# Business_Card.net
KiCad netlist of a schematic drawn in EAGLE
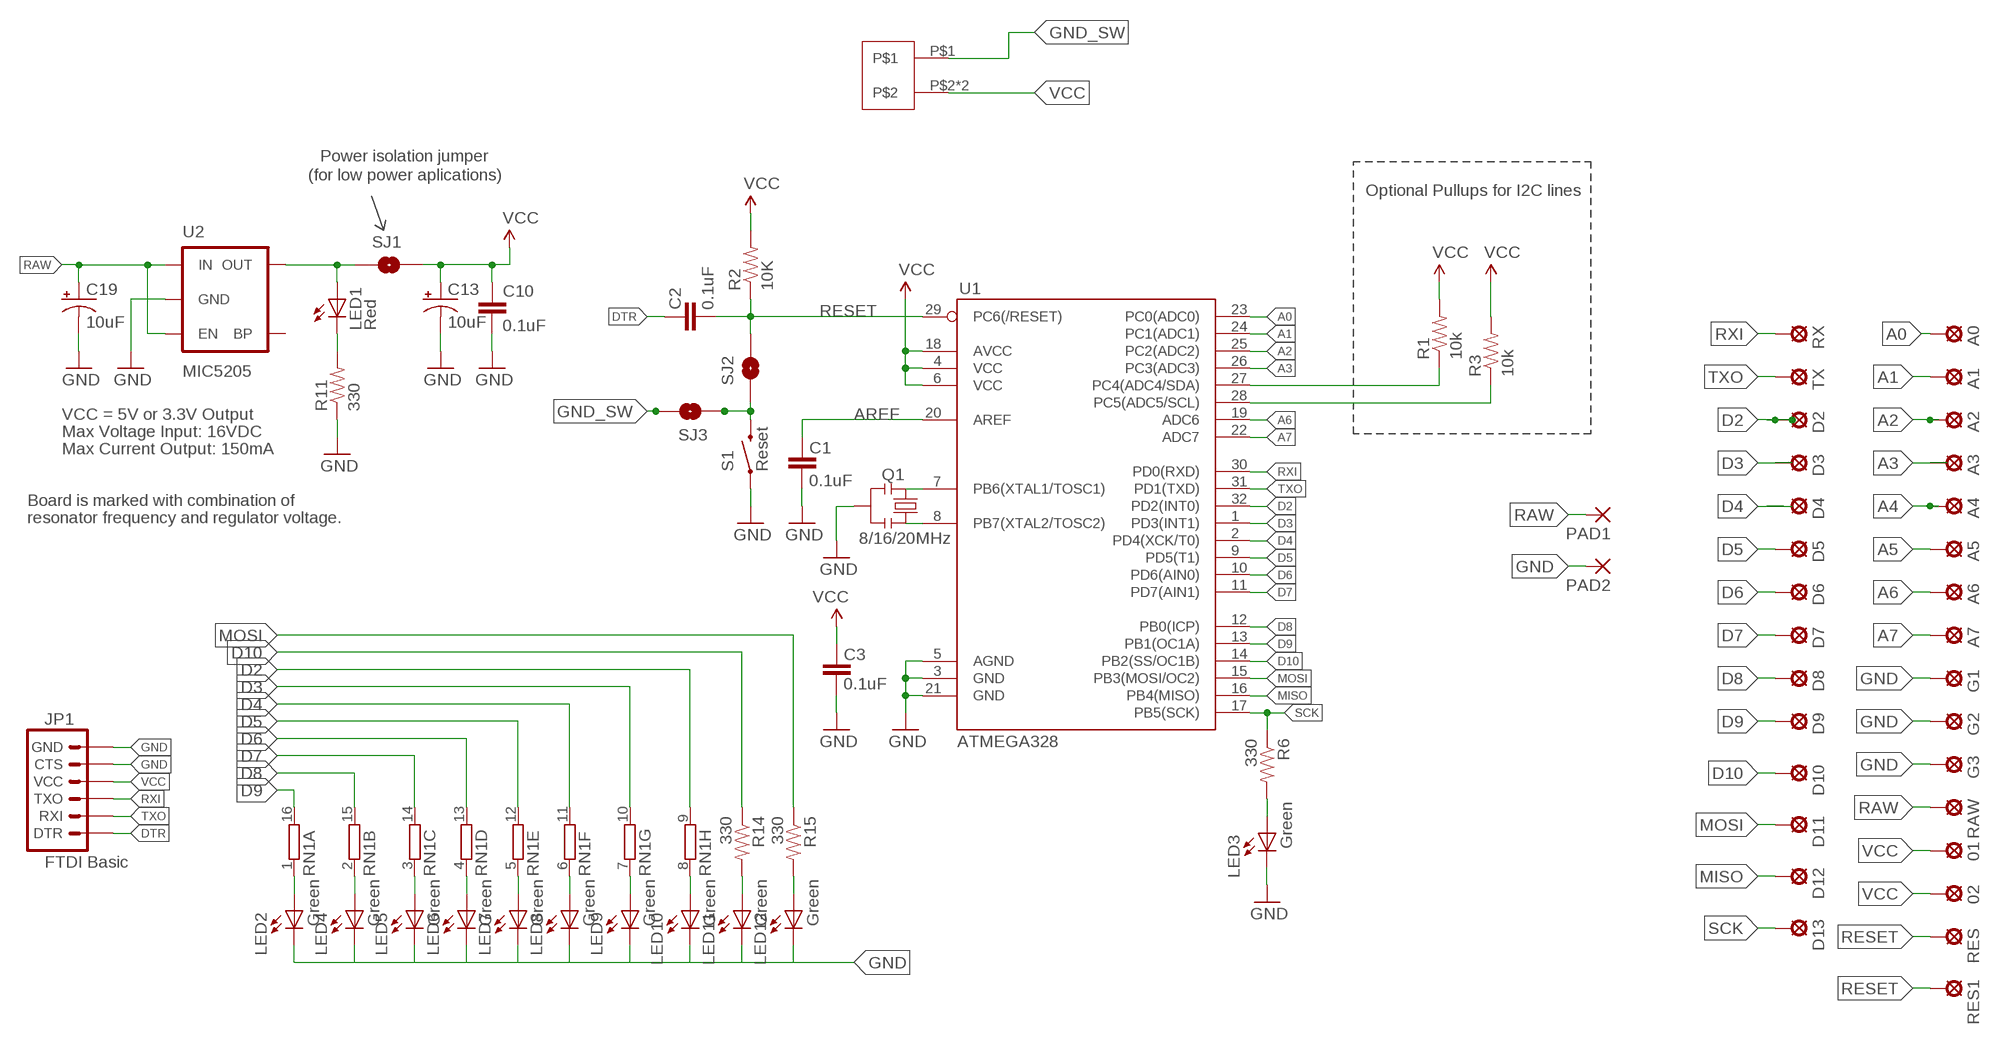
[diagram p0: schematic, sheet 1]

(export (version "E")
  (design (tool "Eeschema 10.0.6"))
  (components
    (comp (ref "01")
      (value "SE13")
      (footprint "eagle-import:SE13")
      (libsource (lib "eagle-import") (part "SE13"))
    )
    (comp (ref "02")
      (value "SE13")
      (footprint "eagle-import:SE13")
      (libsource (lib "eagle-import") (part "SE13"))
    )
    (comp (ref "A0")
      (value "SE13")
      (footprint "eagle-import:SE13")
      (libsource (lib "eagle-import") (part "SE13"))
    )
    (comp (ref "A1")
      (value "SE13")
      (footprint "eagle-import:SE13")
      (libsource (lib "eagle-import") (part "SE13"))
    )
    (comp (ref "A2")
      (value "SE13")
      (footprint "eagle-import:SE13")
      (libsource (lib "eagle-import") (part "SE13"))
    )
    (comp (ref "A3")
      (value "SE13")
      (footprint "eagle-import:SE13")
      (libsource (lib "eagle-import") (part "SE13"))
    )
    (comp (ref "A4")
      (value "SE13")
      (footprint "eagle-import:SE13")
      (libsource (lib "eagle-import") (part "SE13"))
    )
    (comp (ref "A5")
      (value "SE13")
      (footprint "eagle-import:SE13")
      (libsource (lib "eagle-import") (part "SE13"))
    )
    (comp (ref "A6")
      (value "SE13")
      (footprint "eagle-import:SE13")
      (libsource (lib "eagle-import") (part "SE13"))
    )
    (comp (ref "A7")
      (value "SE13")
      (footprint "eagle-import:SE13")
      (libsource (lib "eagle-import") (part "SE13"))
    )
    (comp (ref "C1")
      (value "0.1uF")
      (footprint "eagle-import:0603-CAP")
      (libsource (lib "eagle-import") (part "CAP0603-CAP"))
    )
    (comp (ref "C2")
      (value "0.1uF")
      (footprint "eagle-import:0603-CAP")
      (libsource (lib "eagle-import") (part "CAP0603-CAP"))
    )
    (comp (ref "C3")
      (value "0.1uF")
      (footprint "eagle-import:0603-CAP")
      (libsource (lib "eagle-import") (part "CAP0603-CAP"))
    )
    (comp (ref "C10")
      (value "0.1uF")
      (footprint "eagle-import:0603-CAP")
      (libsource (lib "eagle-import") (part "CAP0603-CAP"))
    )
    (comp (ref "C13")
      (value "10uF")
      (footprint "eagle-import:EIA3216")
      (libsource (lib "eagle-import") (part "CAP_POL1206"))
    )
    (comp (ref "C19")
      (value "10uF")
      (footprint "eagle-import:EIA3216")
      (libsource (lib "eagle-import") (part "CAP_POL1206"))
    )
    (comp (ref "D2")
      (value "SE13")
      (footprint "eagle-import:SE13")
      (libsource (lib "eagle-import") (part "SE13"))
    )
    (comp (ref "D3")
      (value "SE13")
      (footprint "eagle-import:SE13")
      (libsource (lib "eagle-import") (part "SE13"))
    )
    (comp (ref "D4")
      (value "SE13")
      (footprint "eagle-import:SE13")
      (libsource (lib "eagle-import") (part "SE13"))
    )
    (comp (ref "D5")
      (value "SE13")
      (footprint "eagle-import:SE13")
      (libsource (lib "eagle-import") (part "SE13"))
    )
    (comp (ref "D6")
      (value "SE13")
      (footprint "eagle-import:SE13")
      (libsource (lib "eagle-import") (part "SE13"))
    )
    (comp (ref "D7")
      (value "SE13")
      (footprint "eagle-import:SE13")
      (libsource (lib "eagle-import") (part "SE13"))
    )
    (comp (ref "D8")
      (value "SE13")
      (footprint "eagle-import:SE13")
      (libsource (lib "eagle-import") (part "SE13"))
    )
    (comp (ref "D9")
      (value "SE13")
      (footprint "eagle-import:SE13")
      (libsource (lib "eagle-import") (part "SE13"))
    )
    (comp (ref "D10")
      (value "SE13")
      (footprint "eagle-import:SE13")
      (libsource (lib "eagle-import") (part "SE13"))
    )
    (comp (ref "D11")
      (value "SE13")
      (footprint "eagle-import:SE13")
      (libsource (lib "eagle-import") (part "SE13"))
    )
    (comp (ref "D12")
      (value "SE13")
      (footprint "eagle-import:SE13")
      (libsource (lib "eagle-import") (part "SE13"))
    )
    (comp (ref "D13")
      (value "SE13")
      (footprint "eagle-import:SE13")
      (libsource (lib "eagle-import") (part "SE13"))
    )
    (comp (ref "G1")
      (value "SE13")
      (footprint "eagle-import:SE13")
      (libsource (lib "eagle-import") (part "SE13"))
    )
    (comp (ref "G2")
      (value "SE13")
      (footprint "eagle-import:SE13")
      (libsource (lib "eagle-import") (part "SE13"))
    )
    (comp (ref "G3")
      (value "SE13")
      (footprint "eagle-import:SE13")
      (libsource (lib "eagle-import") (part "SE13"))
    )
    (comp (ref "GND_SW")
      (value "CR2032")
      (footprint "eagle-import:CR2032")
      (libsource (lib "eagle-import") (part "CR2032"))
    )
    (comp (ref "JP1")
      (value "FTDI Basic")
      (footprint "eagle-import:1X06")
      (libsource (lib "eagle-import") (part "ARDUINO_SERIAL_PROGRAMPTH"))
    )
    (comp (ref "LED1")
      (value "Red")
      (footprint "eagle-import:0603-LED-ALT1")
      (libsource (lib "eagle-import") (part "LED"))
    )
    (comp (ref "LED2")
      (value "Green")
      (footprint "eagle-import:0603-LED-ALT1")
      (libsource (lib "eagle-import") (part "LED"))
    )
    (comp (ref "LED3")
      (value "Green")
      (footprint "eagle-import:0603-LED-ALT1")
      (libsource (lib "eagle-import") (part "LED"))
    )
    (comp (ref "LED4")
      (value "Green")
      (footprint "eagle-import:0603-LED-ALT1")
      (libsource (lib "eagle-import") (part "LED"))
    )
    (comp (ref "LED5")
      (value "Green")
      (footprint "eagle-import:0603-LED-ALT1")
      (libsource (lib "eagle-import") (part "LED"))
    )
    (comp (ref "LED6")
      (value "Green")
      (footprint "eagle-import:0603-LED-ALT1")
      (libsource (lib "eagle-import") (part "LED"))
    )
    (comp (ref "LED7")
      (value "Green")
      (footprint "eagle-import:0603-LED-ALT1")
      (libsource (lib "eagle-import") (part "LED"))
    )
    (comp (ref "LED8")
      (value "Green")
      (footprint "eagle-import:0603-LED-ALT1")
      (libsource (lib "eagle-import") (part "LED"))
    )
    (comp (ref "LED9")
      (value "Green")
      (footprint "eagle-import:0603-LED-ALT1")
      (libsource (lib "eagle-import") (part "LED"))
    )
    (comp (ref "LED10")
      (value "Green")
      (footprint "eagle-import:0603-LED-ALT1")
      (libsource (lib "eagle-import") (part "LED"))
    )
    (comp (ref "LED11")
      (value "Green")
      (footprint "eagle-import:0603-LED-ALT1")
      (libsource (lib "eagle-import") (part "LED"))
    )
    (comp (ref "LED12")
      (value "Green")
      (footprint "eagle-import:0603-LED-ALT1")
      (libsource (lib "eagle-import") (part "LED"))
    )
    (comp (ref "PAD1")
      (value "2,54/1,1")
      (footprint "eagle-import:2,54_1,1")
      (libsource (lib "eagle-import") (part "2,54/1,1"))
    )
    (comp (ref "PAD2")
      (value "2,54/1,1")
      (footprint "eagle-import:2,54_1,1")
      (libsource (lib "eagle-import") (part "2,54/1,1"))
    )
    (comp (ref "Q1")
      (value "8/16/20MHz")
      (footprint "eagle-import:RESONATOR-SMD-1_1")
      (libsource (lib "eagle-import") (part "RESONATOR1{colon}1"))
    )
    (comp (ref "R1")
      (value "10k")
      (footprint "eagle-import:0603-RES")
      (libsource (lib "eagle-import") (part "RESISTOR0603-RES"))
    )
    (comp (ref "R2")
      (value "10K")
      (footprint "eagle-import:0603-RES")
      (libsource (lib "eagle-import") (part "RESISTOR0603-RES"))
    )
    (comp (ref "R3")
      (value "10k")
      (footprint "eagle-import:0603-RES")
      (libsource (lib "eagle-import") (part "RESISTOR0603-RES"))
    )
    (comp (ref "R6")
      (value "330")
      (footprint "eagle-import:0603-RES")
      (libsource (lib "eagle-import") (part "RESISTOR0603-RES"))
    )
    (comp (ref "R11")
      (value "330")
      (footprint "eagle-import:0603-RES")
      (libsource (lib "eagle-import") (part "RESISTOR0603-RES"))
    )
    (comp (ref "R14")
      (value "330")
      (footprint "eagle-import:0603-RES")
      (libsource (lib "eagle-import") (part "RESISTOR0603-RES"))
    )
    (comp (ref "R15")
      (value "330")
      (footprint "eagle-import:0603-RES")
      (libsource (lib "eagle-import") (part "RESISTOR0603-RES"))
    )
    (comp (ref "RAW")
      (value "SE13")
      (footprint "eagle-import:SE13")
      (libsource (lib "eagle-import") (part "SE13"))
    )
    (comp (ref "RES")
      (value "SE13")
      (footprint "eagle-import:SE13")
      (libsource (lib "eagle-import") (part "SE13"))
    )
    (comp (ref "RES1")
      (value "SE13")
      (footprint "eagle-import:SE13")
      (libsource (lib "eagle-import") (part "SE13"))
    )
    (comp (ref "RN1")
      (value "8R-NSOMC")
      (footprint "eagle-import:SOMC16")
      (libsource (lib "eagle-import") (part "8R-NSOMC"))
    )
    (comp (ref "RX")
      (value "SE13")
      (footprint "eagle-import:SE13")
      (libsource (lib "eagle-import") (part "SE13"))
    )
    (comp (ref "S1")
      (value "Reset")
      (footprint "eagle-import:TACTILE-SWITCH-SMD-ALT01")
      (libsource (lib "eagle-import") (part "SWITCH-MOMENTARY-2SMD-ALT01"))
    )
    (comp (ref "SJ1")
      (value "SOLDERJUMPERNC")
      (footprint "eagle-import:SJ_2S")
      (libsource (lib "eagle-import") (part "SOLDERJUMPERNC"))
    )
    (comp (ref "SJ2")
      (value "SOLDERJUMPERNC")
      (footprint "eagle-import:SJ_2S")
      (libsource (lib "eagle-import") (part "SOLDERJUMPERNC"))
    )
    (comp (ref "SJ3")
      (value "SOLDERJUMPERNC")
      (footprint "eagle-import:SJ_2S")
      (libsource (lib "eagle-import") (part "SOLDERJUMPERNC"))
    )
    (comp (ref "TX")
      (value "SE13")
      (footprint "eagle-import:SE13")
      (libsource (lib "eagle-import") (part "SE13"))
    )
    (comp (ref "U1")
      (value "ATMEGA328")
      (footprint "eagle-import:TQFP32-08")
      (libsource (lib "eagle-import") (part "ATMEGA168"))
    )
    (comp (ref "U2")
      (value "MIC5205")
      (footprint "eagle-import:SOT23-5")
      (libsource (lib "eagle-import") (part "V_REG_LDOSMD"))
    )
  )
  (nets
    (net (code "1") (name "/AREF") (class "Default")
      (node (ref "C1") (pin "2") (pinfunction "2_2") (pintype "passive"))
      (node (ref "U1") (pin "20") (pinfunction "AREF_20") (pintype "bidirectional"))
    )
    (net (code "2") (name "A0") (class "Default")
      (node (ref "A0") (pin "MP") (pinfunction "MP_MP") (pintype "passive"))
      (node (ref "U1") (pin "23") (pinfunction "PC0(ADC0)_23") (pintype "bidirectional"))
    )
    (net (code "3") (name "A1") (class "Default")
      (node (ref "A1") (pin "MP") (pinfunction "MP_MP") (pintype "passive"))
      (node (ref "U1") (pin "24") (pinfunction "PC1(ADC1)_24") (pintype "bidirectional"))
    )
    (net (code "4") (name "A2") (class "Default")
      (node (ref "A2") (pin "MP") (pinfunction "MP_MP") (pintype "passive"))
      (node (ref "U1") (pin "25") (pinfunction "PC2(ADC2)_25") (pintype "bidirectional"))
    )
    (net (code "5") (name "A3") (class "Default")
      (node (ref "A3") (pin "MP") (pinfunction "MP_MP") (pintype "passive"))
      (node (ref "U1") (pin "26") (pinfunction "PC3(ADC3)_26") (pintype "bidirectional"))
    )
    (net (code "6") (name "A4") (class "Default")
      (node (ref "A4") (pin "MP") (pinfunction "MP_MP") (pintype "passive"))
      (node (ref "R1") (pin "1") (pinfunction "1_1") (pintype "passive"))
      (node (ref "U1") (pin "27") (pinfunction "PC4(ADC4/SDA)_27") (pintype "bidirectional"))
    )
    (net (code "7") (name "A5") (class "Default")
      (node (ref "A5") (pin "MP") (pinfunction "MP_MP") (pintype "passive"))
      (node (ref "R3") (pin "1") (pinfunction "1_1") (pintype "passive"))
      (node (ref "U1") (pin "28") (pinfunction "PC5(ADC5/SCL)_28") (pintype "bidirectional"))
    )
    (net (code "8") (name "A6") (class "Default")
      (node (ref "A6") (pin "MP") (pinfunction "MP_MP") (pintype "passive"))
      (node (ref "U1") (pin "19") (pinfunction "ADC6_19") (pintype "bidirectional"))
    )
    (net (code "9") (name "A7") (class "Default")
      (node (ref "A7") (pin "MP") (pinfunction "MP_MP") (pintype "passive"))
      (node (ref "U1") (pin "22") (pinfunction "ADC7_22") (pintype "bidirectional"))
    )
    (net (code "10") (name "D2") (class "Default")
      (node (ref "D2") (pin "MP") (pinfunction "MP_MP") (pintype "passive"))
      (node (ref "RN1") (pin "9") (pinfunction "2_9") (pintype "passive"))
      (node (ref "U1") (pin "32") (pinfunction "PD2(INT0)_32") (pintype "bidirectional"))
    )
    (net (code "11") (name "D3") (class "Default")
      (node (ref "D3") (pin "MP") (pinfunction "MP_MP") (pintype "passive"))
      (node (ref "RN1") (pin "10") (pinfunction "2_10") (pintype "passive"))
      (node (ref "U1") (pin "1") (pinfunction "PD3(INT1)_1") (pintype "bidirectional"))
    )
    (net (code "12") (name "D4") (class "Default")
      (node (ref "D4") (pin "MP") (pinfunction "MP_MP") (pintype "passive"))
      (node (ref "RN1") (pin "11") (pinfunction "2_11") (pintype "passive"))
      (node (ref "U1") (pin "2") (pinfunction "PD4(XCK/T0)_2") (pintype "bidirectional"))
    )
    (net (code "13") (name "D5") (class "Default")
      (node (ref "D5") (pin "MP") (pinfunction "MP_MP") (pintype "passive"))
      (node (ref "RN1") (pin "12") (pinfunction "2_12") (pintype "passive"))
      (node (ref "U1") (pin "9") (pinfunction "PD5(T1)_9") (pintype "bidirectional"))
    )
    (net (code "14") (name "D6") (class "Default")
      (node (ref "D6") (pin "MP") (pinfunction "MP_MP") (pintype "passive"))
      (node (ref "RN1") (pin "13") (pinfunction "2_13") (pintype "passive"))
      (node (ref "U1") (pin "10") (pinfunction "PD6(AIN0)_10") (pintype "bidirectional"))
    )
    (net (code "15") (name "D7") (class "Default")
      (node (ref "D7") (pin "MP") (pinfunction "MP_MP") (pintype "passive"))
      (node (ref "RN1") (pin "14") (pinfunction "2_14") (pintype "passive"))
      (node (ref "U1") (pin "11") (pinfunction "PD7(AIN1)_11") (pintype "bidirectional"))
    )
    (net (code "16") (name "D8") (class "Default")
      (node (ref "D8") (pin "MP") (pinfunction "MP_MP") (pintype "passive"))
      (node (ref "RN1") (pin "15") (pinfunction "2_15") (pintype "passive"))
      (node (ref "U1") (pin "12") (pinfunction "PB0(ICP)_12") (pintype "bidirectional"))
    )
    (net (code "17") (name "D9") (class "Default")
      (node (ref "D9") (pin "MP") (pinfunction "MP_MP") (pintype "passive"))
      (node (ref "RN1") (pin "16") (pinfunction "2_16") (pintype "passive"))
      (node (ref "U1") (pin "13") (pinfunction "PB1(OC1A)_13") (pintype "bidirectional"))
    )
    (net (code "18") (name "D10") (class "Default")
      (node (ref "D10") (pin "MP") (pinfunction "MP_MP") (pintype "passive"))
      (node (ref "R14") (pin "1") (pinfunction "1_1") (pintype "passive"))
      (node (ref "U1") (pin "14") (pinfunction "PB2(SS/OC1B)_14") (pintype "bidirectional"))
    )
    (net (code "19") (name "DTR") (class "Default")
      (node (ref "C2") (pin "2") (pinfunction "2_2") (pintype "passive"))
      (node (ref "JP1") (pin "1") (pinfunction "DTR_1") (pintype "passive"))
    )
    (net (code "20") (name "GND") (class "Default")
      (node (ref "C1") (pin "1") (pinfunction "1_1") (pintype "passive"))
      (node (ref "C10") (pin "2") (pinfunction "2_2") (pintype "passive"))
      (node (ref "C13") (pin "C") (pinfunction "-_C") (pintype "passive"))
      (node (ref "C19") (pin "C") (pinfunction "-_C") (pintype "passive"))
      (node (ref "C3") (pin "1") (pinfunction "1_1") (pintype "passive"))
      (node (ref "G1") (pin "MP") (pinfunction "MP_MP") (pintype "passive"))
      (node (ref "G2") (pin "MP") (pinfunction "MP_MP") (pintype "passive"))
      (node (ref "G3") (pin "MP") (pinfunction "MP_MP") (pintype "passive"))
      (node (ref "JP1") (pin "5") (pinfunction "CTS_5") (pintype "passive"))
      (node (ref "JP1") (pin "6") (pinfunction "GND_6") (pintype "passive"))
      (node (ref "LED10") (pin "C") (pinfunction "C_C") (pintype "passive"))
      (node (ref "LED11") (pin "C") (pinfunction "C_C") (pintype "passive"))
      (node (ref "LED12") (pin "C") (pinfunction "C_C") (pintype "passive"))
      (node (ref "LED2") (pin "C") (pinfunction "C_C") (pintype "passive"))
      (node (ref "LED3") (pin "C") (pinfunction "C_C") (pintype "passive"))
      (node (ref "LED4") (pin "C") (pinfunction "C_C") (pintype "passive"))
      (node (ref "LED5") (pin "C") (pinfunction "C_C") (pintype "passive"))
      (node (ref "LED6") (pin "C") (pinfunction "C_C") (pintype "passive"))
      (node (ref "LED7") (pin "C") (pinfunction "C_C") (pintype "passive"))
      (node (ref "LED8") (pin "C") (pinfunction "C_C") (pintype "passive"))
      (node (ref "LED9") (pin "C") (pinfunction "C_C") (pintype "passive"))
      (node (ref "PAD2") (pin "1") (pinfunction "P_1") (pintype "passive"))
      (node (ref "Q1") (pin "2") (pinfunction "2_2") (pintype "passive"))
      (node (ref "R11") (pin "1") (pinfunction "1_1") (pintype "passive"))
      (node (ref "S1") (pin "1") (pinfunction "1_1") (pintype "passive"))
      (node (ref "S1") (pin "2") (pinfunction "1_2") (pintype "passive"))
      (node (ref "U1") (pin "21") (pinfunction "GND_21") (pintype "bidirectional"))
      (node (ref "U1") (pin "3") (pinfunction "GND_3") (pintype "bidirectional"))
      (node (ref "U1") (pin "5") (pinfunction "AGND_5") (pintype "bidirectional"))
      (node (ref "U2") (pin "2") (pinfunction "GND_2") (pintype "input"))
    )
    (net (code "21") (name "GND_SW") (class "Default")
      (node (ref "GND_SW") (pin "P$1") (pinfunction "P$1_P$1") (pintype "bidirectional"))
      (node (ref "SJ3") (pin "2") (pinfunction "2_2") (pintype "passive"))
    )
    (net (code "22") (name "MISO") (class "Default")
      (node (ref "D12") (pin "MP") (pinfunction "MP_MP") (pintype "passive"))
      (node (ref "U1") (pin "16") (pinfunction "PB4(MISO)_16") (pintype "bidirectional"))
    )
    (net (code "23") (name "MOSI") (class "Default")
      (node (ref "D11") (pin "MP") (pinfunction "MP_MP") (pintype "passive"))
      (node (ref "R15") (pin "1") (pinfunction "1_1") (pintype "passive"))
      (node (ref "U1") (pin "15") (pinfunction "PB3(MOSI/OC2)_15") (pintype "bidirectional"))
    )
    (net (code "24") (name "Net-(LED1-PadC)") (class "Default")
      (node (ref "LED1") (pin "C") (pinfunction "C_C") (pintype "passive"))
      (node (ref "R11") (pin "2") (pinfunction "2_2") (pintype "passive"))
    )
    (net (code "25") (name "Net-(LED2-PadA)") (class "Default")
      (node (ref "LED2") (pin "A") (pinfunction "A_A") (pintype "passive"))
      (node (ref "RN1") (pin "1") (pinfunction "1_1") (pintype "passive"))
    )
    (net (code "26") (name "Net-(LED3-PadA)") (class "Default")
      (node (ref "LED3") (pin "A") (pinfunction "A_A") (pintype "passive"))
      (node (ref "R6") (pin "2") (pinfunction "2_2") (pintype "passive"))
    )
    (net (code "27") (name "Net-(LED11-PadA)") (class "Default")
      (node (ref "LED11") (pin "A") (pinfunction "A_A") (pintype "passive"))
      (node (ref "R14") (pin "2") (pinfunction "2_2") (pintype "passive"))
    )
    (net (code "28") (name "Net-(LED12-PadA)") (class "Default")
      (node (ref "LED12") (pin "A") (pinfunction "A_A") (pintype "passive"))
      (node (ref "R15") (pin "2") (pinfunction "2_2") (pintype "passive"))
    )
    (net (code "29") (name "Net-(RN1B-1)") (class "Default")
      (node (ref "LED4") (pin "A") (pinfunction "A_A") (pintype "passive"))
      (node (ref "RN1") (pin "2") (pinfunction "1_2") (pintype "passive"))
    )
    (net (code "30") (name "Net-(RN1C-1)") (class "Default")
      (node (ref "LED5") (pin "A") (pinfunction "A_A") (pintype "passive"))
      (node (ref "RN1") (pin "3") (pinfunction "1_3") (pintype "passive"))
    )
    (net (code "31") (name "Net-(RN1D-1)") (class "Default")
      (node (ref "LED6") (pin "A") (pinfunction "A_A") (pintype "passive"))
      (node (ref "RN1") (pin "4") (pinfunction "1_4") (pintype "passive"))
    )
    (net (code "32") (name "Net-(RN1E-1)") (class "Default")
      (node (ref "LED7") (pin "A") (pinfunction "A_A") (pintype "passive"))
      (node (ref "RN1") (pin "5") (pinfunction "1_5") (pintype "passive"))
    )
    (net (code "33") (name "Net-(RN1F-1)") (class "Default")
      (node (ref "LED8") (pin "A") (pinfunction "A_A") (pintype "passive"))
      (node (ref "RN1") (pin "6") (pinfunction "1_6") (pintype "passive"))
    )
    (net (code "34") (name "Net-(RN1G-1)") (class "Default")
      (node (ref "LED9") (pin "A") (pinfunction "A_A") (pintype "passive"))
      (node (ref "RN1") (pin "7") (pinfunction "1_7") (pintype "passive"))
    )
    (net (code "35") (name "Net-(RN1H-1)") (class "Default")
      (node (ref "LED10") (pin "A") (pinfunction "A_A") (pintype "passive"))
      (node (ref "RN1") (pin "8") (pinfunction "1_8") (pintype "passive"))
    )
    (net (code "36") (name "Net-(S1-2-Pad3)") (class "Default")
      (node (ref "S1") (pin "3") (pinfunction "2_3") (pintype "passive"))
      (node (ref "S1") (pin "4") (pinfunction "2_4") (pintype "passive"))
      (node (ref "SJ2") (pin "1") (pinfunction "1_1") (pintype "passive"))
      (node (ref "SJ3") (pin "1") (pinfunction "1_1") (pintype "passive"))
    )
    (net (code "37") (name "Net-(U1-PB6(XTAL1{slash}TOSC1))") (class "Default")
      (node (ref "Q1") (pin "1") (pinfunction "1_1") (pintype "passive"))
      (node (ref "U1") (pin "7") (pinfunction "PB6(XTAL1/TOSC1)_7") (pintype "bidirectional"))
    )
    (net (code "38") (name "Net-(U1-PB7(XTAL2{slash}TOSC2))") (class "Default")
      (node (ref "Q1") (pin "3") (pinfunction "3_3") (pintype "passive"))
      (node (ref "U1") (pin "8") (pinfunction "PB7(XTAL2/TOSC2)_8") (pintype "bidirectional"))
    )
    (net (code "39") (name "Net-(U2-OUT)") (class "Default")
      (node (ref "LED1") (pin "A") (pinfunction "A_A") (pintype "passive"))
      (node (ref "SJ1") (pin "1") (pinfunction "1_1") (pintype "passive"))
      (node (ref "U2") (pin "5") (pinfunction "OUT_5") (pintype "passive"))
    )
    (net (code "40") (name "RAW") (class "Default")
      (node (ref "C19") (pin "A") (pinfunction "+_A") (pintype "passive"))
      (node (ref "PAD1") (pin "1") (pinfunction "P_1") (pintype "passive"))
      (node (ref "RAW") (pin "MP") (pinfunction "MP_MP") (pintype "passive"))
      (node (ref "U2") (pin "1") (pinfunction "IN_1") (pintype "input"))
      (node (ref "U2") (pin "3") (pinfunction "EN_3") (pintype "input"))
    )
    (net (code "41") (name "RESET") (class "Default")
      (node (ref "C2") (pin "1") (pinfunction "1_1") (pintype "passive"))
      (node (ref "R2") (pin "1") (pinfunction "1_1") (pintype "passive"))
      (node (ref "RES") (pin "MP") (pinfunction "MP_MP") (pintype "passive"))
      (node (ref "RES1") (pin "MP") (pinfunction "MP_MP") (pintype "passive"))
      (node (ref "SJ2") (pin "2") (pinfunction "2_2") (pintype "passive"))
      (node (ref "U1") (pin "29") (pinfunction "PC6(/RESET)_29") (pintype "bidirectional"))
    )
    (net (code "42") (name "RXI") (class "Default")
      (node (ref "JP1") (pin "3") (pinfunction "TXO_3") (pintype "passive"))
      (node (ref "RX") (pin "MP") (pinfunction "MP_MP") (pintype "passive"))
      (node (ref "U1") (pin "30") (pinfunction "PD0(RXD)_30") (pintype "bidirectional"))
    )
    (net (code "43") (name "SCK") (class "Default")
      (node (ref "D13") (pin "MP") (pinfunction "MP_MP") (pintype "passive"))
      (node (ref "R6") (pin "1") (pinfunction "1_1") (pintype "passive"))
      (node (ref "U1") (pin "17") (pinfunction "PB5(SCK)_17") (pintype "bidirectional"))
    )
    (net (code "44") (name "TXO") (class "Default")
      (node (ref "JP1") (pin "2") (pinfunction "RXI_2") (pintype "passive"))
      (node (ref "TX") (pin "MP") (pinfunction "MP_MP") (pintype "passive"))
      (node (ref "U1") (pin "31") (pinfunction "PD1(TXD)_31") (pintype "bidirectional"))
    )
    (net (code "45") (name "VCC") (class "Default")
      (node (ref "01") (pin "MP") (pinfunction "MP_MP") (pintype "passive"))
      (node (ref "02") (pin "MP") (pinfunction "MP_MP") (pintype "passive"))
      (node (ref "C10") (pin "1") (pinfunction "1_1") (pintype "passive"))
      (node (ref "C13") (pin "A") (pinfunction "+_A") (pintype "passive"))
      (node (ref "C3") (pin "2") (pinfunction "2_2") (pintype "passive"))
      (node (ref "GND_SW") (pin "P$2") (pinfunction "P$2_P$2") (pintype "bidirectional"))
      (node (ref "GND_SW") (pin "P$3") (pinfunction "P$2_P$3") (pintype "bidirectional"))
      (node (ref "JP1") (pin "4") (pinfunction "VCC_4") (pintype "passive"))
      (node (ref "R1") (pin "2") (pinfunction "2_2") (pintype "passive"))
      (node (ref "R2") (pin "2") (pinfunction "2_2") (pintype "passive"))
      (node (ref "R3") (pin "2") (pinfunction "2_2") (pintype "passive"))
      (node (ref "SJ1") (pin "2") (pinfunction "2_2") (pintype "passive"))
      (node (ref "U1") (pin "18") (pinfunction "AVCC_18") (pintype "bidirectional"))
      (node (ref "U1") (pin "4") (pinfunction "VCC_4") (pintype "bidirectional"))
      (node (ref "U1") (pin "6") (pinfunction "VCC_6") (pintype "bidirectional"))
    )
    (net (code "46") (name "unconnected-(U2-BP-Pad4)") (class "Default")
      (node (ref "U2") (pin "4") (pinfunction "BP_4") (pintype "input"))
    )
  )
)
